# BOC_VGA_KB_MOUSE.net
KiCad netlist of a schematic drawn in Altium Designer
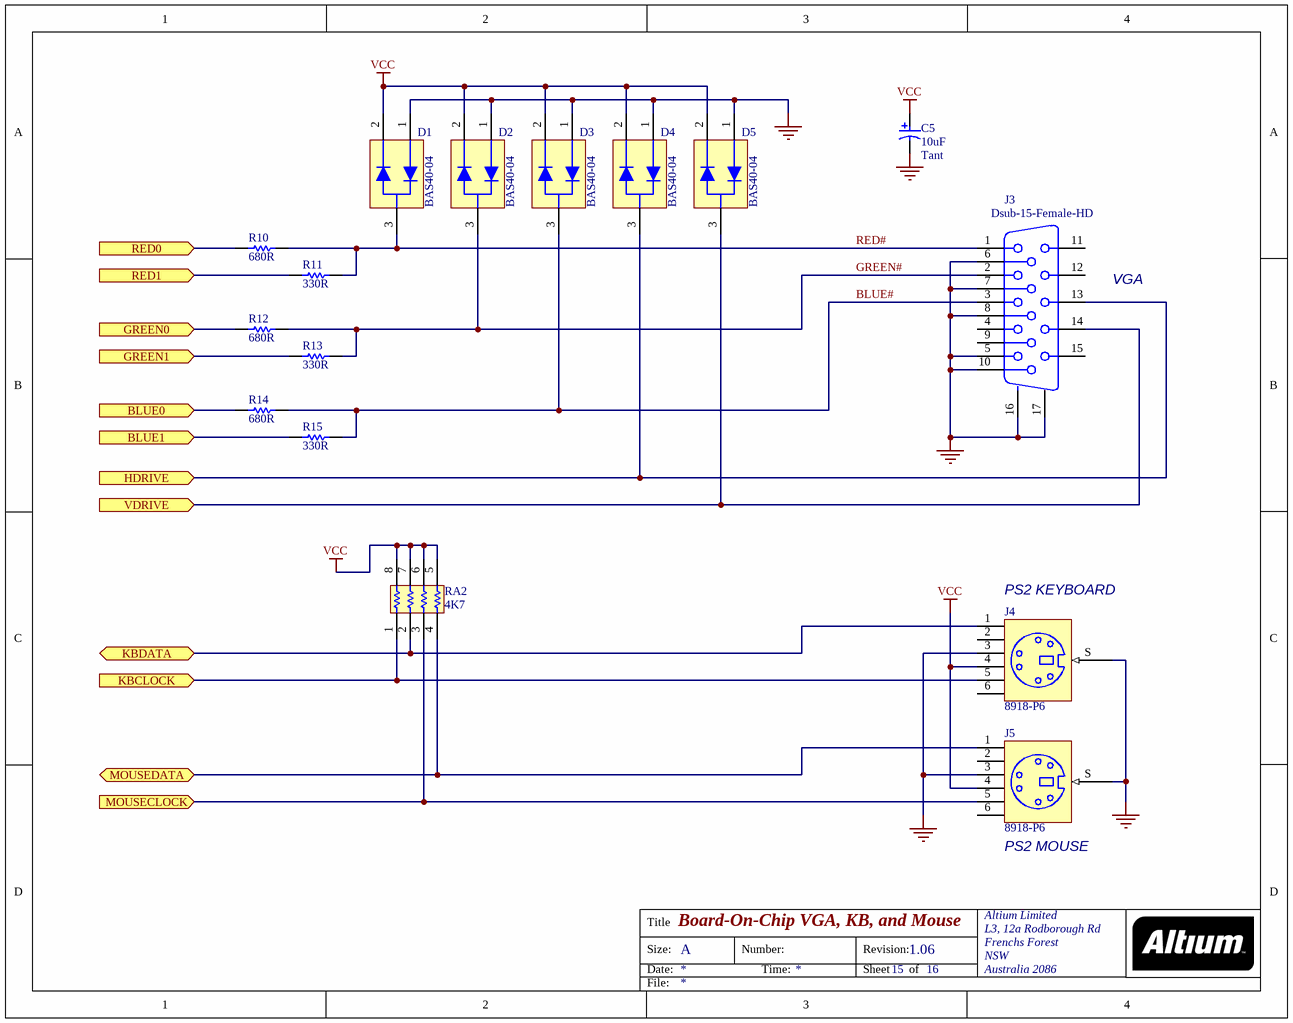
[diagram p0: BOC_VGA_KB_MOUSE.SchDoc]

(export (version "E")
  (design (tool "Eeschema 10.0.6"))
  (components
    (comp (ref "C5")
      (value "10uF")
      (footprint "Altium Nanoboard Project:MCCT-B")
      (description "Polar Capacitor")
      (fields (field (name "CAPACITOR TYPE") "Tant"))
      (libsource (lib "Altium Nanoboard Project") (part "CAP_POLAR"))
    )
    (comp (ref "D1")
      (value "BAS40-04")
      (footprint "Altium Nanoboard Project:SO-G3")
      (description "Shottky Diode Pair")
      (libsource (lib "Altium Nanoboard Project") (part "BAS40-04"))
    )
    (comp (ref "D2")
      (value "BAS40-04")
      (footprint "Altium Nanoboard Project:SO-G3")
      (description "Shottky Diode Pair")
      (libsource (lib "Altium Nanoboard Project") (part "BAS40-04"))
    )
    (comp (ref "D3")
      (value "BAS40-04")
      (footprint "Altium Nanoboard Project:SO-G3")
      (description "Shottky Diode Pair")
      (libsource (lib "Altium Nanoboard Project") (part "BAS40-04"))
    )
    (comp (ref "D4")
      (value "BAS40-04")
      (footprint "Altium Nanoboard Project:SO-G3")
      (description "Shottky Diode Pair")
      (libsource (lib "Altium Nanoboard Project") (part "BAS40-04"))
    )
    (comp (ref "D5")
      (value "BAS40-04")
      (footprint "Altium Nanoboard Project:SO-G3")
      (description "Shottky Diode Pair")
      (libsource (lib "Altium Nanoboard Project") (part "BAS40-04"))
    )
    (comp (ref "J3")
      (value "Dsub-15-Female-HD")
      (footprint "Altium Nanoboard Project:DB15-VGA-Female")
      (description "Dsub-15 High density VGA Female connetor")
      (fields (field (name "MANUFACTURER") "Generic Components") (field (name "PUBLISHER") "Altium Limited"))
      (libsource (lib "Altium Nanoboard Project") (part "Dsub-15-Female-HD"))
    )
    (comp (ref "J4")
      (value "8918-P6")
      (footprint "Altium Nanoboard Project:PS2-6PIN")
      (description "6 Pin Through Hole PS2 Socket (Kycon P/N)")
      (libsource (lib "Altium Nanoboard Project") (part "PS2-6PIN"))
    )
    (comp (ref "J5")
      (value "8918-P6")
      (footprint "Altium Nanoboard Project:PS2-6PIN")
      (description "6 Pin Through Hole PS2 Socket (Kycon P/N)")
      (libsource (lib "Altium Nanoboard Project") (part "PS2-6PIN"))
    )
    (comp (ref "R10")
      (value "680R")
      (footprint "Altium Nanoboard Project:CC2012-0805")
      (description "Resistor")
      (libsource (lib "Altium Nanoboard Project") (part "RES"))
    )
    (comp (ref "R11")
      (value "330R")
      (footprint "Altium Nanoboard Project:CC2012-0805")
      (description "Resistor")
      (libsource (lib "Altium Nanoboard Project") (part "RES"))
    )
    (comp (ref "R12")
      (value "680R")
      (footprint "Altium Nanoboard Project:CC2012-0805")
      (description "Resistor")
      (libsource (lib "Altium Nanoboard Project") (part "RES"))
    )
    (comp (ref "R13")
      (value "330R")
      (footprint "Altium Nanoboard Project:CC2012-0805")
      (description "Resistor")
      (libsource (lib "Altium Nanoboard Project") (part "RES"))
    )
    (comp (ref "R14")
      (value "680R")
      (footprint "Altium Nanoboard Project:CC2012-0805")
      (description "Resistor")
      (libsource (lib "Altium Nanoboard Project") (part "RES"))
    )
    (comp (ref "R15")
      (value "330R")
      (footprint "Altium Nanoboard Project:CC2012-0805")
      (description "Resistor")
      (libsource (lib "Altium Nanoboard Project") (part "RES"))
    )
    (comp (ref "RA2")
      (value "4K7")
      (footprint "Altium Nanoboard Project:MNR34")
      (description "3216x4 Resistor Array")
      (libsource (lib "Altium Nanoboard Project") (part "MNR34"))
    )
  )
  (nets
    (net (code "1") (name "/BLUE#") (class "Default")
      (node (ref "D3") (pin "3") (pintype "passive"))
      (node (ref "J3") (pin "3") (pinfunction "3_3") (pintype "passive"))
      (node (ref "R14") (pin "2") (pinfunction "2_2") (pintype "passive"))
      (node (ref "R15") (pin "2") (pinfunction "2_2") (pintype "passive"))
    )
    (net (code "2") (name "/BLUE0") (class "Default")
      (node (ref "R14") (pin "1") (pinfunction "1_1") (pintype "passive"))
    )
    (net (code "3") (name "/BLUE1") (class "Default")
      (node (ref "R15") (pin "1") (pinfunction "1_1") (pintype "passive"))
    )
    (net (code "4") (name "/GREEN#") (class "Default")
      (node (ref "D2") (pin "3") (pintype "passive"))
      (node (ref "J3") (pin "2") (pinfunction "2_2") (pintype "passive"))
      (node (ref "R12") (pin "2") (pinfunction "2_2") (pintype "passive"))
      (node (ref "R13") (pin "2") (pinfunction "2_2") (pintype "passive"))
    )
    (net (code "5") (name "/GREEN0") (class "Default")
      (node (ref "R12") (pin "1") (pinfunction "1_1") (pintype "passive"))
    )
    (net (code "6") (name "/GREEN1") (class "Default")
      (node (ref "R13") (pin "1") (pinfunction "1_1") (pintype "passive"))
    )
    (net (code "7") (name "/HDRIVE") (class "Default")
      (node (ref "D4") (pin "3") (pintype "passive"))
      (node (ref "J3") (pin "13") (pinfunction "13_13") (pintype "passive"))
    )
    (net (code "8") (name "/KBCLOCK") (class "Default")
      (node (ref "J4") (pin "5") (pintype "passive"))
      (node (ref "RA2") (pin "1") (pintype "passive"))
    )
    (net (code "9") (name "/KBDATA") (class "Default")
      (node (ref "J4") (pin "1") (pintype "passive"))
      (node (ref "RA2") (pin "2") (pintype "passive"))
    )
    (net (code "10") (name "/MOUSECLOCK") (class "Default")
      (node (ref "J5") (pin "5") (pintype "passive"))
      (node (ref "RA2") (pin "3") (pintype "passive"))
    )
    (net (code "11") (name "/MOUSEDATA") (class "Default")
      (node (ref "J5") (pin "1") (pintype "passive"))
      (node (ref "RA2") (pin "4") (pintype "passive"))
    )
    (net (code "12") (name "/RED#") (class "Default")
      (node (ref "D1") (pin "3") (pintype "passive"))
      (node (ref "J3") (pin "1") (pinfunction "1_1") (pintype "passive"))
      (node (ref "R10") (pin "2") (pinfunction "2_2") (pintype "passive"))
      (node (ref "R11") (pin "2") (pinfunction "2_2") (pintype "passive"))
    )
    (net (code "13") (name "/RED0") (class "Default")
      (node (ref "R10") (pin "1") (pinfunction "1_1") (pintype "passive"))
    )
    (net (code "14") (name "/RED1") (class "Default")
      (node (ref "R11") (pin "1") (pinfunction "1_1") (pintype "passive"))
    )
    (net (code "15") (name "/VDRIVE") (class "Default")
      (node (ref "D5") (pin "3") (pintype "passive"))
      (node (ref "J3") (pin "14") (pinfunction "14_14") (pintype "passive"))
    )
    (net (code "16") (name "GND") (class "Default")
      (node (ref "C5") (pin "2") (pinfunction "2_2") (pintype "passive"))
      (node (ref "D1") (pin "1") (pintype "passive"))
      (node (ref "D2") (pin "1") (pintype "passive"))
      (node (ref "D3") (pin "1") (pintype "passive"))
      (node (ref "D4") (pin "1") (pintype "passive"))
      (node (ref "D5") (pin "1") (pintype "passive"))
      (node (ref "J3") (pin "10") (pinfunction "10_10") (pintype "power_in"))
      (node (ref "J3") (pin "16") (pinfunction "MH1_16") (pintype "passive"))
      (node (ref "J3") (pin "17") (pinfunction "MH2_17") (pintype "passive"))
      (node (ref "J3") (pin "5") (pinfunction "5_5") (pintype "power_in"))
      (node (ref "J3") (pin "6") (pinfunction "6_6") (pintype "power_in"))
      (node (ref "J3") (pin "7") (pinfunction "7_7") (pintype "power_in"))
      (node (ref "J3") (pin "8") (pinfunction "8_8") (pintype "power_in"))
      (node (ref "J4") (pin "3") (pintype "passive"))
      (node (ref "J4") (pin "S") (pintype "input"))
      (node (ref "J5") (pin "3") (pintype "passive"))
      (node (ref "J5") (pin "S") (pintype "input"))
    )
    (net (code "17") (name "VCC") (class "Default")
      (node (ref "C5") (pin "1") (pinfunction "1_1") (pintype "passive"))
      (node (ref "D1") (pin "2") (pintype "passive"))
      (node (ref "D2") (pin "2") (pintype "passive"))
      (node (ref "D3") (pin "2") (pintype "passive"))
      (node (ref "D4") (pin "2") (pintype "passive"))
      (node (ref "D5") (pin "2") (pintype "passive"))
      (node (ref "J4") (pin "4") (pintype "passive"))
      (node (ref "J5") (pin "4") (pintype "passive"))
      (node (ref "RA2") (pin "5") (pintype "passive"))
      (node (ref "RA2") (pin "6") (pintype "passive"))
      (node (ref "RA2") (pin "7") (pintype "passive"))
      (node (ref "RA2") (pin "8") (pintype "passive"))
    )
    (net (code "18") (name "unconnected-(J3-Pad4)") (class "Default")
      (node (ref "J3") (pin "4") (pinfunction "4_4") (pintype "passive"))
    )
    (net (code "19") (name "unconnected-(J3-Pad9)") (class "Default")
      (node (ref "J3") (pin "9") (pinfunction "9_9") (pintype "passive"))
    )
    (net (code "20") (name "unconnected-(J3-Pad11)") (class "Default")
      (node (ref "J3") (pin "11") (pinfunction "11_11") (pintype "power_in"))
    )
    (net (code "21") (name "unconnected-(J3-Pad12)") (class "Default")
      (node (ref "J3") (pin "12") (pinfunction "12_12") (pintype "passive"))
    )
    (net (code "22") (name "unconnected-(J3-Pad15)") (class "Default")
      (node (ref "J3") (pin "15") (pinfunction "15_15") (pintype "passive"))
    )
    (net (code "23") (name "unconnected-(J4-Pad2)") (class "Default")
      (node (ref "J4") (pin "2") (pintype "passive"))
    )
    (net (code "24") (name "unconnected-(J4-Pad6)") (class "Default")
      (node (ref "J4") (pin "6") (pintype "passive"))
    )
    (net (code "25") (name "unconnected-(J5-Pad2)") (class "Default")
      (node (ref "J5") (pin "2") (pintype "passive"))
    )
    (net (code "26") (name "unconnected-(J5-Pad6)") (class "Default")
      (node (ref "J5") (pin "6") (pintype "passive"))
    )
  )
)
